# 11_Power_Input_and_Regulators.net
KiCad netlist of a schematic drawn in Altium Designer
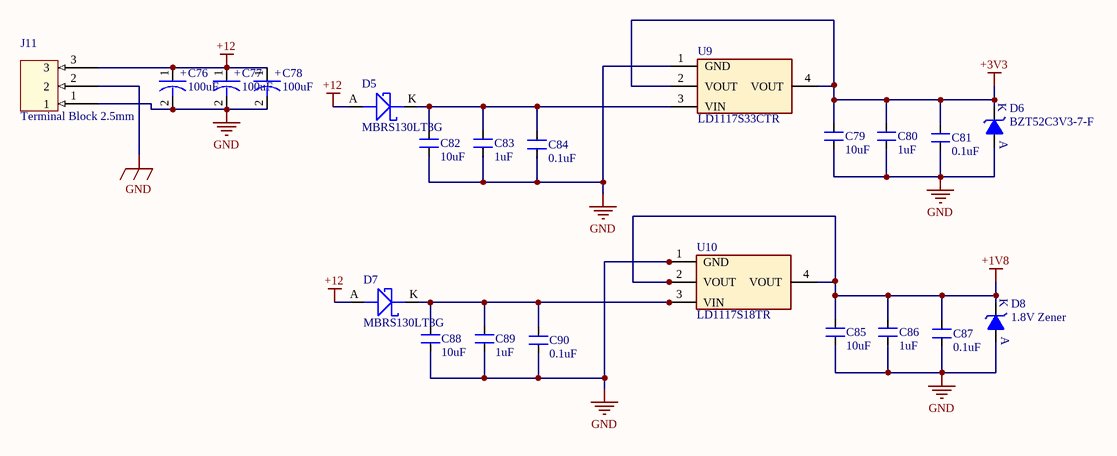
[diagram p0: [11] Power Input and Regulators.SchDoc]

(export (version "E")
  (design (tool "Eeschema 10.0.6"))
  (components
    (comp (ref "C76")
      (value "100uF")
      (footprint "ACAP_P305_D393_H393_RAD")
      (description "100µF 50V Aluminum Polymer Capacitor Radial, Can - SMD 28mOhm 4000 Hrs @ 125°C")
      (fields
        (field (name "MANUFACTURER") "Nichicon")
        (field (name "MANUFACTURER PART NUMBER") "GYA1H101MCQ1GS")
      )
      (libsource (lib "ESTEEMPCBLIB") (part "CAP-P_100uF-50V-20%-RAD"))
    )
    (comp (ref "C77")
      (value "100uF")
      (footprint "ACAP_P305_D393_H393_RAD")
      (description "100µF 50V Aluminum Polymer Capacitor Radial, Can - SMD 28mOhm 4000 Hrs @ 125°C")
      (fields
        (field (name "MANUFACTURER") "Nichicon")
        (field (name "MANUFACTURER PART NUMBER") "GYA1H101MCQ1GS")
      )
      (libsource (lib "ESTEEMPCBLIB") (part "CAP-P_100uF-50V-20%-RAD"))
    )
    (comp (ref "C78")
      (value "100uF")
      (footprint "ACAP_P305_D393_H393_RAD")
      (description "100µF 50V Aluminum Polymer Capacitor Radial, Can - SMD 28mOhm 4000 Hrs @ 125°C")
      (fields
        (field (name "MANUFACTURER") "Nichicon")
        (field (name "MANUFACTURER PART NUMBER") "GYA1H101MCQ1GS")
      )
      (libsource (lib "ESTEEMPCBLIB") (part "CAP-P_100uF-50V-20%-RAD"))
    )
    (comp (ref "C79")
      (value "10uF")
      (footprint "CAP_1206")
      (description "10µF ±10% 50V Ceramic Capacitor X7R 1206 (3216 Metric)")
      (fields
        (field (name "MANUFACTURER") "KEMET")
        (field (name "MANUFACTURER PART NUMBER") "CL31B106KBHNNNE")
      )
      (libsource (lib "ESTEEMPCBLIB") (part "CAP_10uF-50V-10%-1206"))
    )
    (comp (ref "C80")
      (value "1uF")
      (footprint "CAP_0805")
      (description "1µF ±5% 50V Ceramic Capacitor X7R 0805 (2012 Metric)")
      (fields
        (field (name "MANUFACTURER") "Samsung")
        (field (name "MANUFACTURER PART NUMBER") "CC0805JKX7R9BB105")
      )
      (libsource (lib "ESTEEMPCBLIB") (part "CAP_1uF-50V-5%-0805"))
    )
    (comp (ref "C81")
      (value "0.1uF")
      (footprint "CAP_0805")
      (description "0.1µF ±10% 50V Ceramic Capacitor X7R 0805 (2012 Metric)")
      (fields
        (field (name "MANUFACTURER") "Samsung")
        (field (name "MANUFACTURER PART NUMBER") "CL21B104KBCNNNC")
      )
      (libsource (lib "ESTEEMPCBLIB") (part "CAP_0.1uF-50V-10%-0805"))
    )
    (comp (ref "C82")
      (value "10uF")
      (footprint "CAP_1206")
      (description "10µF ±10% 50V Ceramic Capacitor X7R 1206 (3216 Metric)")
      (fields
        (field (name "MANUFACTURER") "KEMET")
        (field (name "MANUFACTURER PART NUMBER") "CL31B106KBHNNNE")
      )
      (libsource (lib "ESTEEMPCBLIB") (part "CAP_10uF-50V-10%-1206"))
    )
    (comp (ref "C83")
      (value "1uF")
      (footprint "CAP_0805")
      (description "1µF ±5% 50V Ceramic Capacitor X7R 0805 (2012 Metric)")
      (fields
        (field (name "MANUFACTURER") "Samsung")
        (field (name "MANUFACTURER PART NUMBER") "CC0805JKX7R9BB105")
      )
      (libsource (lib "ESTEEMPCBLIB") (part "CAP_1uF-50V-5%-0805"))
    )
    (comp (ref "C84")
      (value "0.1uF")
      (footprint "CAP_0805")
      (description "0.1µF ±10% 50V Ceramic Capacitor X7R 0805 (2012 Metric)")
      (fields
        (field (name "MANUFACTURER") "Samsung")
        (field (name "MANUFACTURER PART NUMBER") "CL21B104KBCNNNC")
      )
      (libsource (lib "ESTEEMPCBLIB") (part "CAP_0.1uF-50V-10%-0805"))
    )
    (comp (ref "C85")
      (value "10uF")
      (footprint "CAP_1206")
      (description "10µF ±10% 50V Ceramic Capacitor X7R 1206 (3216 Metric)")
      (fields
        (field (name "MANUFACTURER") "KEMET")
        (field (name "MANUFACTURER PART NUMBER") "CL31B106KBHNNNE")
      )
      (libsource (lib "ESTEEMPCBLIB") (part "CAP_10uF-50V-10%-1206"))
    )
    (comp (ref "C86")
      (value "1uF")
      (footprint "CAP_0805")
      (description "1µF ±5% 50V Ceramic Capacitor X7R 0805 (2012 Metric)")
      (fields
        (field (name "MANUFACTURER") "Samsung")
        (field (name "MANUFACTURER PART NUMBER") "CC0805JKX7R9BB105")
      )
      (libsource (lib "ESTEEMPCBLIB") (part "CAP_1uF-50V-5%-0805"))
    )
    (comp (ref "C87")
      (value "0.1uF")
      (footprint "CAP_0805")
      (description "0.1µF ±10% 50V Ceramic Capacitor X7R 0805 (2012 Metric)")
      (fields
        (field (name "MANUFACTURER") "Samsung")
        (field (name "MANUFACTURER PART NUMBER") "CL21B104KBCNNNC")
      )
      (libsource (lib "ESTEEMPCBLIB") (part "CAP_0.1uF-50V-10%-0805"))
    )
    (comp (ref "C88")
      (value "10uF")
      (footprint "CAP_1206")
      (description "10µF ±10% 50V Ceramic Capacitor X7R 1206 (3216 Metric)")
      (fields
        (field (name "MANUFACTURER") "KEMET")
        (field (name "MANUFACTURER PART NUMBER") "CL31B106KBHNNNE")
      )
      (libsource (lib "ESTEEMPCBLIB") (part "CAP_10uF-50V-10%-1206"))
    )
    (comp (ref "C89")
      (value "1uF")
      (footprint "CAP_0805")
      (description "1µF ±5% 50V Ceramic Capacitor X7R 0805 (2012 Metric)")
      (fields
        (field (name "MANUFACTURER") "Samsung")
        (field (name "MANUFACTURER PART NUMBER") "CC0805JKX7R9BB105")
      )
      (libsource (lib "ESTEEMPCBLIB") (part "CAP_1uF-50V-5%-0805"))
    )
    (comp (ref "C90")
      (value "0.1uF")
      (footprint "CAP_0805")
      (description "0.1µF ±10% 50V Ceramic Capacitor X7R 0805 (2012 Metric)")
      (fields
        (field (name "MANUFACTURER") "Samsung")
        (field (name "MANUFACTURER PART NUMBER") "CL21B104KBCNNNC")
      )
      (libsource (lib "ESTEEMPCBLIB") (part "CAP_0.1uF-50V-10%-0805"))
    )
    (comp (ref "D5")
      (value "MBRS130LT3G")
      (footprint "DIO_SMB_DO-214AA")
      (description "Diode Schottky 30V 2A Surface Mount SMB")
      (fields (field (name "MANUFACTURER") "ON Semiconductor"))
      (libsource (lib "ESTEEMPCBLIB") (part "DIO-S_445mV-30V-2A-SMB"))
    )
    (comp (ref "D6")
      (value "BZT52C3V3-7-F")
      (footprint "DIO_SOD-123")
      (description "Zener Diode 3.3V 500mW ±6% Surface Mount SOD-123")
      (fields (field (name "MANUFACTURER") "Diodes Incorporated"))
      (libsource (lib "ESTEEMPCBLIB") (part "DIO-Z_3.3V-500mW-SOD123"))
    )
    (comp (ref "D7")
      (value "MBRS130LT3G")
      (footprint "DIO_SMB_DO-214AA")
      (description "Diode Schottky 30V 2A Surface Mount SMB")
      (fields (field (name "MANUFACTURER") "ON Semiconductor"))
      (libsource (lib "ESTEEMPCBLIB") (part "DIO-S_445mV-30V-2A-SMB"))
    )
    (comp (ref "D8")
      (value "1.8V Zener")
      (footprint "DIO_DO-213AB_SMD")
      (description "Zener Diode 1.8V 500mW ±5% Surface Mount DO-213AA")
      (libsource (lib "ESTEEMPCBLIB") (part "DIO-Z_1.8V-500mW-DO213AA"))
    )
    (comp (ref "J11")
      (value "Terminal Block 2.5mm")
      (footprint "CON3_100_TB_TH_ST")
      (description "3 Pins, 1 Row 2.54mm Pitch, straight Connector, male")
      (fields
        (field (name "MANUFACTURER PART NUMBER") "1725669")
        (field (name "MANUFACTURER") "Phoenix Contact")
      )
      (libsource (lib "ESTEEMPCBLIB") (part "CON-TB_3X1-100-ST-TH"))
    )
    (comp (ref "U9")
      (value "LD1117S33CTR")
      (footprint "SOT223_3")
      (description "Linear Voltage Regulator IC 1 Output 800mA SOT-223")
      (fields (field (name "MANUFACTURER") "STMicroelectronics"))
      (libsource (lib "ESTEEMPCBLIB") (part "REG_15V-3.3V-0.9A-12W-SOT223"))
    )
    (comp (ref "U10")
      (value "LD1117S18TR")
      (footprint "SOT223_3")
      (description "LDO Voltage Regulators 1.8V 0.8A Positive")
      (fields (field (name "MANUFACTURER") "STMicroelectronics"))
      (libsource (lib "ESTEEMPCBLIB") (part "REG_15V-1.8V-0.8A-1.4W-SOT223"))
    )
  )
  (nets
    (net (code "1") (name "+1V8") (class "Default")
      (node (ref "C85") (pin "2") (pinfunction "2_2") (pintype "passive"))
      (node (ref "C86") (pin "2") (pinfunction "2_2") (pintype "passive"))
      (node (ref "C87") (pin "2") (pinfunction "2_2") (pintype "passive"))
      (node (ref "D8") (pin "K") (pinfunction "K_K") (pintype "passive"))
      (node (ref "U10") (pin "2") (pinfunction "VOUT_2") (pintype "passive"))
      (node (ref "U10") (pin "4") (pinfunction "VOUT_4") (pintype "passive"))
    )
    (net (code "2") (name "+3V3") (class "Default")
      (node (ref "C79") (pin "2") (pinfunction "2_2") (pintype "passive"))
      (node (ref "C80") (pin "2") (pinfunction "2_2") (pintype "passive"))
      (node (ref "C81") (pin "2") (pinfunction "2_2") (pintype "passive"))
      (node (ref "D6") (pin "K") (pinfunction "K_K") (pintype "passive"))
      (node (ref "U9") (pin "2") (pinfunction "VOUT_2") (pintype "passive"))
      (node (ref "U9") (pin "4") (pinfunction "VOUT_4") (pintype "passive"))
    )
    (net (code "3") (name "+12") (class "Default")
      (node (ref "C76") (pin "1") (pinfunction "1_1") (pintype "passive"))
      (node (ref "C77") (pin "1") (pinfunction "1_1") (pintype "passive"))
      (node (ref "C78") (pin "1") (pinfunction "1_1") (pintype "passive"))
      (node (ref "D5") (pin "A") (pinfunction "A_A") (pintype "passive"))
      (node (ref "D7") (pin "A") (pinfunction "A_A") (pintype "passive"))
      (node (ref "J11") (pin "3") (pinfunction "3_3") (pintype "input"))
    )
    (net (code "4") (name "GND") (class "Default")
      (node (ref "C76") (pin "2") (pinfunction "2_2") (pintype "passive"))
      (node (ref "C77") (pin "2") (pinfunction "2_2") (pintype "passive"))
      (node (ref "C78") (pin "2") (pinfunction "2_2") (pintype "passive"))
      (node (ref "C79") (pin "1") (pinfunction "1_1") (pintype "passive"))
      (node (ref "C80") (pin "1") (pinfunction "1_1") (pintype "passive"))
      (node (ref "C81") (pin "1") (pinfunction "1_1") (pintype "passive"))
      (node (ref "C82") (pin "1") (pinfunction "1_1") (pintype "passive"))
      (node (ref "C83") (pin "1") (pinfunction "1_1") (pintype "passive"))
      (node (ref "C84") (pin "1") (pinfunction "1_1") (pintype "passive"))
      (node (ref "C85") (pin "1") (pinfunction "1_1") (pintype "passive"))
      (node (ref "C86") (pin "1") (pinfunction "1_1") (pintype "passive"))
      (node (ref "C87") (pin "1") (pinfunction "1_1") (pintype "passive"))
      (node (ref "C88") (pin "1") (pinfunction "1_1") (pintype "passive"))
      (node (ref "C89") (pin "1") (pinfunction "1_1") (pintype "passive"))
      (node (ref "C90") (pin "1") (pinfunction "1_1") (pintype "passive"))
      (node (ref "D6") (pin "A") (pinfunction "A_A") (pintype "passive"))
      (node (ref "D8") (pin "A") (pinfunction "A_A") (pintype "passive"))
      (node (ref "J11") (pin "1") (pinfunction "1_1") (pintype "input"))
      (node (ref "J11") (pin "2") (pinfunction "2_2") (pintype "input"))
      (node (ref "U10") (pin "1") (pinfunction "GND_1") (pintype "passive"))
      (node (ref "U9") (pin "1") (pinfunction "GND_1") (pintype "passive"))
    )
    (net (code "5") (name "Net-(U9-VIN)") (class "Default")
      (node (ref "C82") (pin "2") (pinfunction "2_2") (pintype "passive"))
      (node (ref "C83") (pin "2") (pinfunction "2_2") (pintype "passive"))
      (node (ref "C84") (pin "2") (pinfunction "2_2") (pintype "passive"))
      (node (ref "D5") (pin "K") (pinfunction "K_K") (pintype "passive"))
      (node (ref "U9") (pin "3") (pinfunction "VIN_3") (pintype "passive"))
    )
    (net (code "6") (name "Net-(U10-VIN)") (class "Default")
      (node (ref "C88") (pin "2") (pinfunction "2_2") (pintype "passive"))
      (node (ref "C89") (pin "2") (pinfunction "2_2") (pintype "passive"))
      (node (ref "C90") (pin "2") (pinfunction "2_2") (pintype "passive"))
      (node (ref "D7") (pin "K") (pinfunction "K_K") (pintype "passive"))
      (node (ref "U10") (pin "3") (pinfunction "VIN_3") (pintype "passive"))
    )
  )
)
